# 3_power.net
KiCad netlist of a schematic drawn in Altium Designer
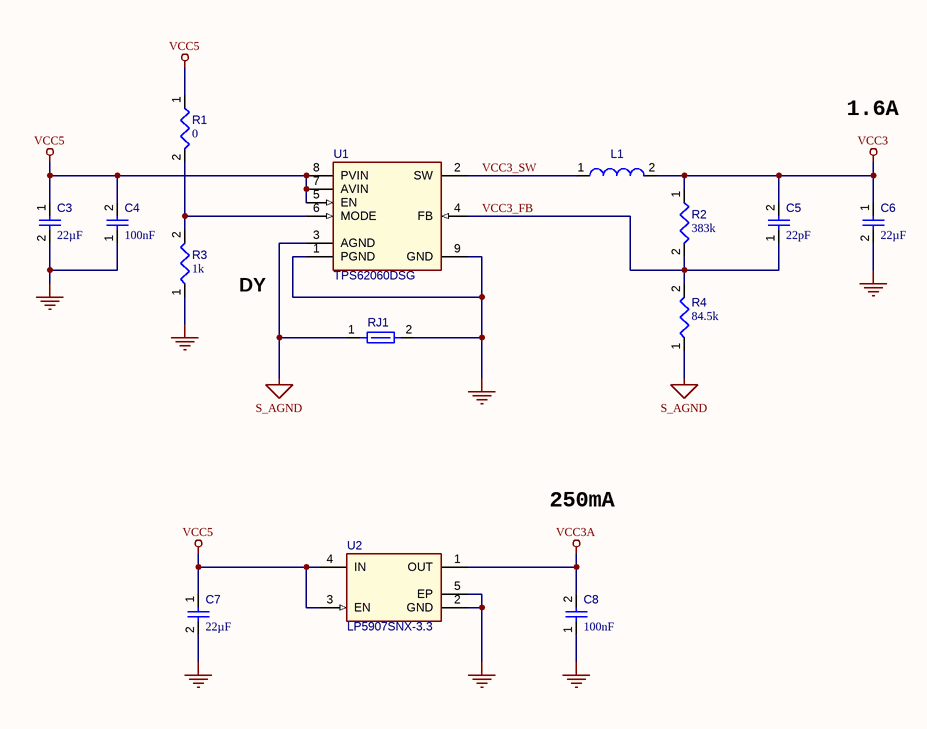
[diagram p0:  3_power.SchDoc]

(export (version "E")
  (design (tool "Eeschema 10.0.6"))
  (components
    (comp (ref "C3")
      (value "22µF")
      (footprint "CAPC0805(2012)145_L")
      (description "Chip Capacitor, 22µF +/-40%, 16V, 0805, Thickness 1.45 mm")
      (fields (field (name "TOLERANCE") "5%") (field (name "Comment") "Capacitor 22µF +/-40% 16V 0805"))
      (libsource (lib "MHH -  Altium Advanced Course A365 01") (part "CAP-NP-2"))
    )
    (comp (ref "C4")
      (value "100nF")
      (footprint "CAPC0402(1005)60_L")
      (description "Chip Capacitor, 100nF +/-20%, 10V, 0402, Thickness 0.6 mm")
      (fields (field (name "TOLERANCE") "20%") (field (name "Comment") "Capacitor 100nF +/-20% 10V 0402"))
      (libsource (lib "MHH -  Altium Advanced Course A365 01") (part "CAP-NP-2"))
    )
    (comp (ref "C5")
      (value "22pF")
      (footprint "CAPC0402(1005)60_L")
      (description "Chip Capacitor, 22pF +/-10%, 50V, 0402, Thickness 0.6 mm")
      (fields (field (name "TOLERANCE") "10%") (field (name "Comment") "Capacitor 22pF +/-10% 50V 0402"))
      (libsource (lib "MHH -  Altium Advanced Course A365 01") (part "CAP-NP-2"))
    )
    (comp (ref "C6")
      (value "22µF")
      (footprint "CAPC0805(2012)145_L")
      (description "Chip Capacitor, 22µF +/-40%, 16V, 0805, Thickness 1.45 mm")
      (fields (field (name "TOLERANCE") "5%") (field (name "Comment") "Capacitor 22µF +/-40% 16V 0805"))
      (libsource (lib "MHH -  Altium Advanced Course A365 01") (part "CAP-NP-2"))
    )
    (comp (ref "C7")
      (value "22µF")
      (footprint "CAPC0805(2012)145_L")
      (description "Chip Capacitor, 22µF +/-40%, 16V, 0805, Thickness 1.45 mm")
      (fields (field (name "TOLERANCE") "5%") (field (name "Comment") "Capacitor 22µF +/-40% 16V 0805"))
      (libsource (lib "MHH -  Altium Advanced Course A365 01") (part "CAP-NP-2"))
    )
    (comp (ref "C8")
      (value "100nF")
      (footprint "CAPC0402(1005)60_L")
      (description "Chip Capacitor, 100nF +/-20%, 10V, 0402, Thickness 0.6 mm")
      (fields (field (name "TOLERANCE") "20%") (field (name "Comment") "Capacitor 100nF +/-20% 10V 0402"))
      (libsource (lib "MHH -  Altium Advanced Course A365 01") (part "CAP-NP-2"))
    )
    (comp (ref "L1")
      (value "VLS252010HBX-2R2M-1")
      (footprint "TDK-VLS252010_V")
      (description "Inductor for Power Circuit, 2.2 uH, +/- 20%, -40 to 105 degC, 2-Pin SMD, RoHS, Tape and Reel")
      (fields (field (name "TOLERANCE") "20%"))
      (libsource (lib "MHH -  Altium Advanced Course A365 01") (part "CMP-001-0020-1"))
    )
    (comp (ref "R1")
      (value "0")
      (footprint "RESC0402(1005)_L")
      (description "Jumper 0402")
      (libsource (lib "MHH -  Altium Advanced Course A365 01") (part "RES-2"))
    )
    (comp (ref "R2")
      (value "383k")
      (footprint "RESC0402(1005)_L")
      (description "Chip Resistor, 383 kOhms, +/-1 %, 63 mW, -55 to 155 degC, 0402")
      (fields (field (name "TOLERANCE") "1%") (field (name "POWER") "63mW"))
      (libsource (lib "MHH -  Altium Advanced Course A365 01") (part "RES-2"))
    )
    (comp (ref "R3")
      (value "1k")
      (footprint "RESC0402(1005)_L")
      (description "Chip Resistor, 1 kOhms, +/-5 %, 63 mW, -55 to 155 degC, 0402")
      (fields (field (name "TOLERANCE") "5%") (field (name "POWER") "63mW"))
      (libsource (lib "MHH -  Altium Advanced Course A365 01") (part "RES-2"))
    )
    (comp (ref "R4")
      (value "84.5k")
      (footprint "RESC0402(1005)_L")
      (description "Chip Resistor, 84,5 kOhms, +/-1 %, 63 mW, -55 to 155 degC, 0402")
      (fields (field (name "TOLERANCE") "1%") (field (name "POWER") "63mW"))
      (libsource (lib "MHH -  Altium Advanced Course A365 01") (part "RES-2"))
    )
    (comp (ref "RJ1")
      (value "Net Tie 10x8mil")
      (footprint "New footprint 1")
      (libsource (lib "MHH -  Altium Advanced Course A365 01") (part "CMP-00022-00002-2"))
    )
    (comp (ref "U1")
      (value "TPS62060DSG")
      (footprint "DSG0008A_V")
      (description "Step Down Converter, 3 MHz, 1.6 A, -45 to 85 degC, 8-Pin WSON, RoHS, Tape and Reel")
      (libsource (lib "MHH -  Altium Advanced Course A365 01") (part "CMP-00002-13_2"))
    )
    (comp (ref "U2")
      (value "LP5907SNX-3.3")
      (footprint "TI-DQN4-480X480TP_V")
      (description "Ultra-Low-Noise, Low-IQ LDO, 3.3 V, 0.25 A, -40 to 125 degC, 4-Pin X2SON, RoHS, Tape and Reel")
      (libsource (lib "MHH -  Altium Advanced Course A365 01") (part "CMP-00094-7"))
    )
  )
  (nets
    (net (code "1") (name "/VCC3_FB") (class "Default")
      (node (ref "C5") (pin "1") (pinfunction "1_1") (pintype "passive"))
      (node (ref "R2") (pin "2") (pinfunction "2_2") (pintype "passive"))
      (node (ref "R4") (pin "2") (pinfunction "2_2") (pintype "passive"))
      (node (ref "U1") (pin "4") (pinfunction "FB_4") (pintype "input"))
    )
    (net (code "2") (name "/VCC3_SW") (class "Default")
      (node (ref "L1") (pin "1") (pinfunction "1_1") (pintype "passive"))
      (node (ref "U1") (pin "2") (pinfunction "SW_2") (pintype "power_in"))
    )
    (net (code "3") (name "GND") (class "Default")
      (node (ref "C3") (pin "2") (pinfunction "2_2") (pintype "passive"))
      (node (ref "C4") (pin "1") (pinfunction "1_1") (pintype "passive"))
      (node (ref "C6") (pin "2") (pinfunction "2_2") (pintype "passive"))
      (node (ref "C7") (pin "2") (pinfunction "2_2") (pintype "passive"))
      (node (ref "C8") (pin "1") (pinfunction "1_1") (pintype "passive"))
      (node (ref "R3") (pin "1") (pinfunction "1_1") (pintype "passive"))
      (node (ref "RJ1") (pin "2") (pinfunction "2_2") (pintype "passive"))
      (node (ref "U1") (pin "1") (pinfunction "PGND_1") (pintype "power_in"))
      (node (ref "U1") (pin "9") (pinfunction "GND_9") (pintype "power_in"))
      (node (ref "U2") (pin "2") (pinfunction "GND_2") (pintype "power_in"))
      (node (ref "U2") (pin "5") (pinfunction "EP_5") (pintype "power_in"))
    )
    (net (code "4") (name "Net-(U1-MODE)") (class "Default")
      (node (ref "R1") (pin "2") (pinfunction "2_2") (pintype "passive"))
      (node (ref "R3") (pin "2") (pinfunction "2_2") (pintype "passive"))
      (node (ref "U1") (pin "6") (pinfunction "MODE_6") (pintype "input"))
    )
    (net (code "5") (name "S_AGND") (class "Default")
      (node (ref "R4") (pin "1") (pinfunction "1_1") (pintype "passive"))
      (node (ref "RJ1") (pin "1") (pinfunction "1_1") (pintype "passive"))
      (node (ref "U1") (pin "3") (pinfunction "AGND_3") (pintype "power_in"))
    )
    (net (code "6") (name "VCC3") (class "Default")
      (node (ref "C5") (pin "2") (pinfunction "2_2") (pintype "passive"))
      (node (ref "C6") (pin "1") (pinfunction "1_1") (pintype "passive"))
      (node (ref "L1") (pin "2") (pinfunction "2_2") (pintype "passive"))
      (node (ref "R2") (pin "1") (pinfunction "1_1") (pintype "passive"))
    )
    (net (code "7") (name "VCC3A") (class "Default")
      (node (ref "C8") (pin "2") (pinfunction "2_2") (pintype "passive"))
      (node (ref "U2") (pin "1") (pinfunction "OUT_1") (pintype "power_in"))
    )
    (net (code "8") (name "VCC5") (class "Default")
      (node (ref "C3") (pin "1") (pinfunction "1_1") (pintype "passive"))
      (node (ref "C4") (pin "2") (pinfunction "2_2") (pintype "passive"))
      (node (ref "C7") (pin "1") (pinfunction "1_1") (pintype "passive"))
      (node (ref "R1") (pin "1") (pinfunction "1_1") (pintype "passive"))
      (node (ref "U1") (pin "5") (pinfunction "EN_5") (pintype "input"))
      (node (ref "U1") (pin "7") (pinfunction "AVIN_7") (pintype "power_in"))
      (node (ref "U1") (pin "8") (pinfunction "PVIN_8") (pintype "power_in"))
      (node (ref "U2") (pin "3") (pinfunction "EN_3") (pintype "input"))
      (node (ref "U2") (pin "4") (pinfunction "IN_4") (pintype "power_in"))
    )
  )
)
